# trackuino_micro_sensor_chip_mk2.net
KiCad netlist of a schematic drawn in EAGLE
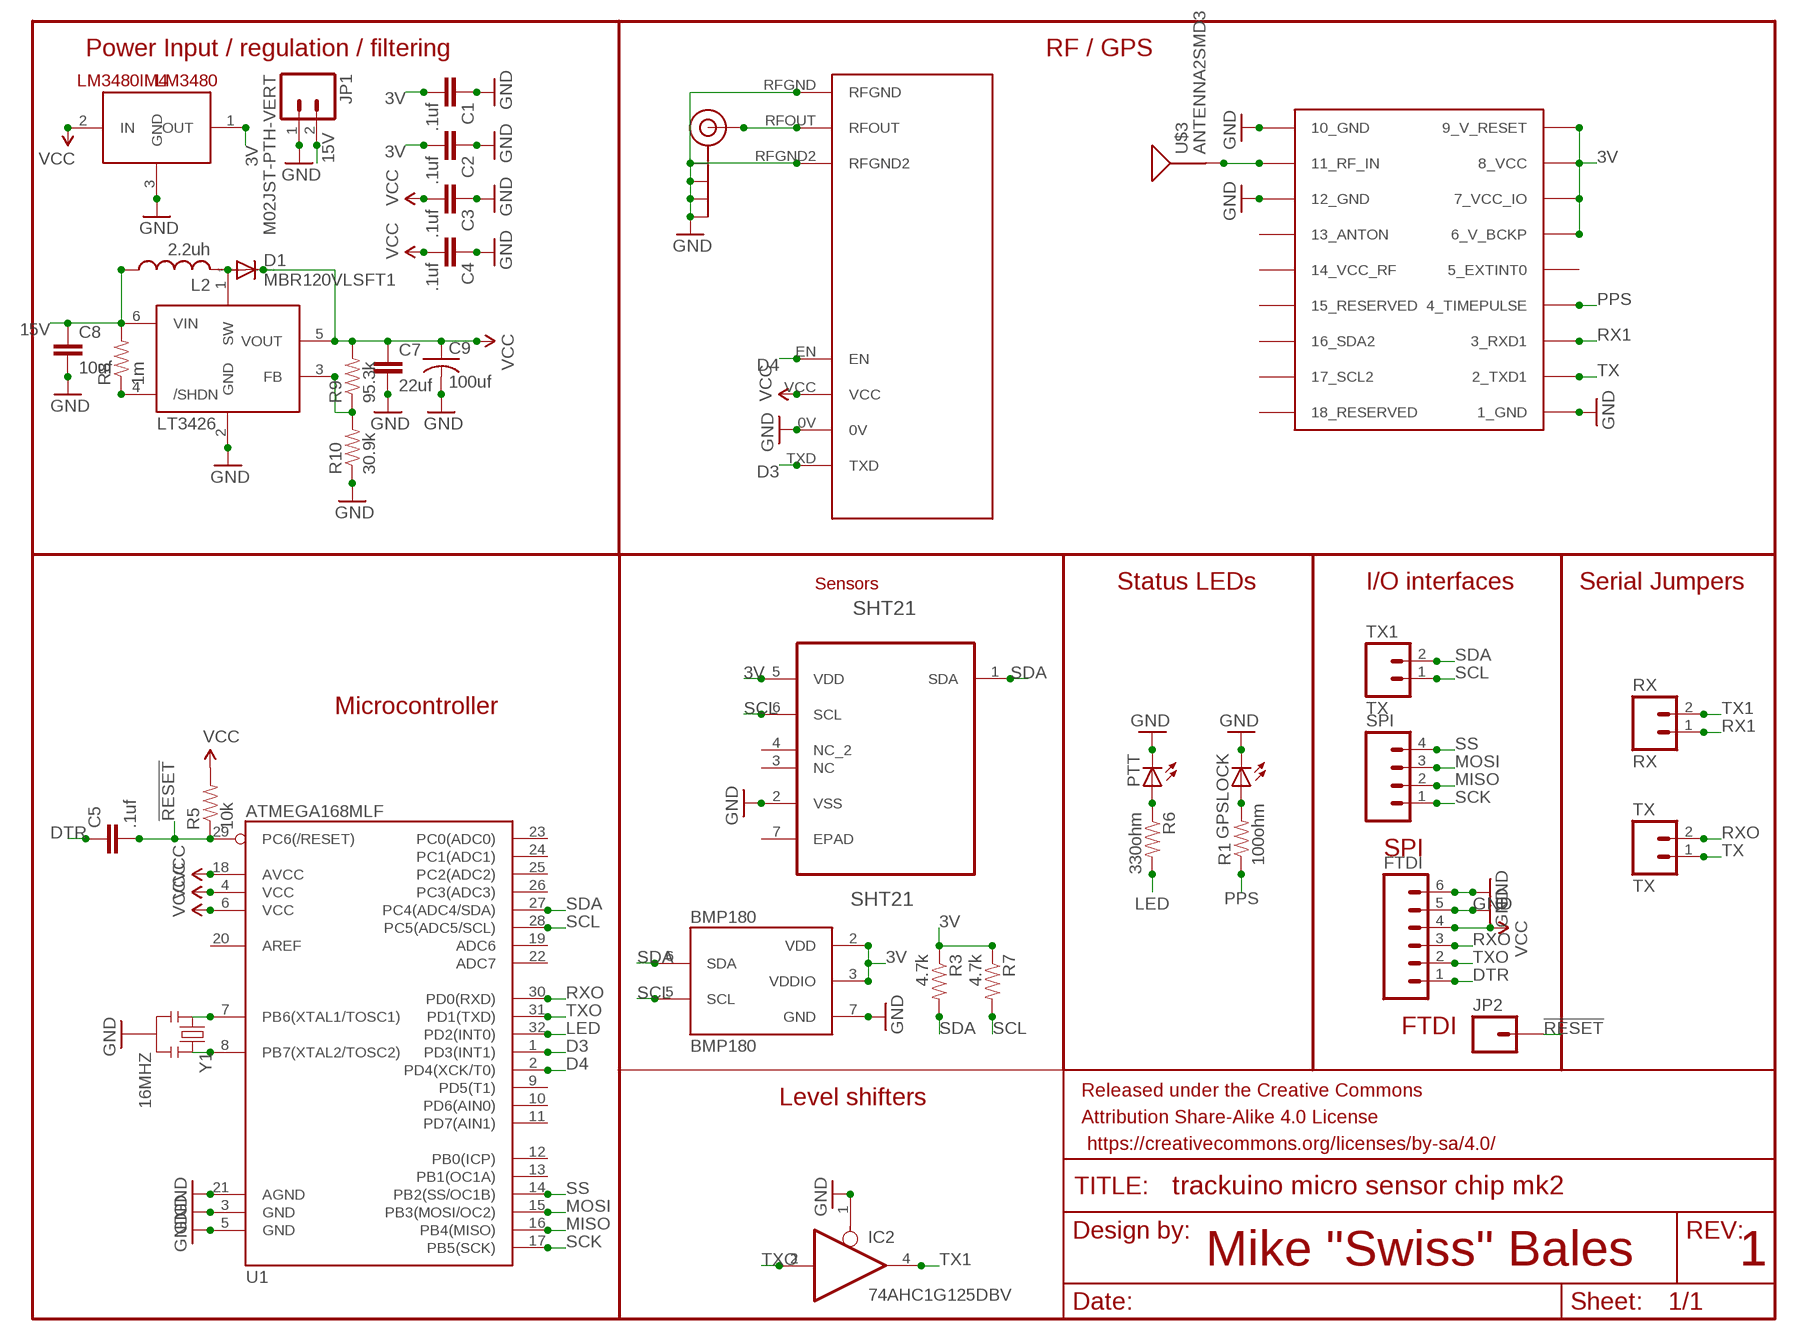
[diagram p0: schematic, sheet 1]

(export (version "E")
  (design (tool "Eeschema 10.0.6"))
  (components
    (comp (ref "BMP180")
      (value "BMP180")
      (footprint "eagle-import:BMP180")
      (libsource (lib "eagle-import") (part "BMP180"))
    )
    (comp (ref "C1")
      (value ".1uf")
      (footprint "eagle-import:0805")
      (libsource (lib "eagle-import") (part "CAP0805"))
    )
    (comp (ref "C2")
      (value ".1uf")
      (footprint "eagle-import:0805")
      (libsource (lib "eagle-import") (part "CAP0805"))
    )
    (comp (ref "C3")
      (value ".1uf")
      (footprint "eagle-import:0805")
      (libsource (lib "eagle-import") (part "CAP0805"))
    )
    (comp (ref "C4")
      (value ".1uf")
      (footprint "eagle-import:0805")
      (libsource (lib "eagle-import") (part "CAP0805"))
    )
    (comp (ref "C5")
      (value ".1uf")
      (footprint "eagle-import:0805")
      (libsource (lib "eagle-import") (part "CAP0805"))
    )
    (comp (ref "C7")
      (value "22uf")
      (footprint "eagle-import:0805")
      (libsource (lib "eagle-import") (part "CAP0805"))
    )
    (comp (ref "C8")
      (value "10uf")
      (footprint "eagle-import:0805")
      (libsource (lib "eagle-import") (part "CAP0805"))
    )
    (comp (ref "C9")
      (value "100uf")
      (footprint "eagle-import:C1206")
      (libsource (lib "eagle-import") (part "C-USC1206"))
    )
    (comp (ref "D1")
      (value "MBR120VLSFT1")
      (footprint "eagle-import:SOD123")
      (libsource (lib "eagle-import") (part "DIODE-SOD123"))
    )
    (comp (ref "FRAME1")
      (value "FRAME-LETTER")
      (footprint "eagle-import:CREATIVE_COMMONS")
      (libsource (lib "eagle-import") (part "FRAME-LETTER"))
    )
    (comp (ref "FTDI")
      (value "M06NO_SILK_FEMALE_PTH")
      (footprint "eagle-import:1X06_NO_SILK")
      (libsource (lib "eagle-import") (part "M06NO_SILK_FEMALE_PTH"))
    )
    (comp (ref "GPSLOCK")
      (value "LEDCHIP-LED0805")
      (footprint "eagle-import:CHIP-LED0805")
      (libsource (lib "eagle-import") (part "LEDCHIP-LED0805"))
    )
    (comp (ref "IC2")
      (value "74AHC1G125DBV")
      (footprint "eagle-import:SOT23-5")
      (libsource (lib "eagle-import") (part "741G125DBVAHC"))
    )
    (comp (ref "J$1")
      (value "SMA_EDGE")
      (footprint "eagle-import:SMA-EDGE")
      (libsource (lib "eagle-import") (part "SMA_EDGE"))
    )
    (comp (ref "JP1")
      (value "M02JST-PTH-VERT")
      (footprint "eagle-import:JST-2-PTH-VERT")
      (libsource (lib "eagle-import") (part "M02JST-PTH-VERT"))
    )
    (comp (ref "JP2")
      (value "M01PTH")
      (footprint "eagle-import:1X01")
      (libsource (lib "eagle-import") (part "M01PTH"))
    )
    (comp (ref "L2")
      (value "2.2uh")
      (footprint "eagle-import:L1812")
      (libsource (lib "eagle-import") (part "L-USL1812"))
    )
    (comp (ref "LM3480")
      (value "LM3480IM4")
      (footprint "eagle-import:SOT23-3")
      (libsource (lib "eagle-import") (part "LM3480IM4"))
    )
    (comp (ref "LT3426")
      (value "LT3426")
      (footprint "eagle-import:SOT23-6")
      (libsource (lib "eagle-import") (part "LT3426"))
    )
    (comp (ref "PTT")
      (value "LEDCHIP-LED0805")
      (footprint "eagle-import:CHIP-LED0805")
      (libsource (lib "eagle-import") (part "LEDCHIP-LED0805"))
    )
    (comp (ref "R1")
      (value "100ohm")
      (footprint "eagle-import:0805")
      (libsource (lib "eagle-import") (part "RESISTOR0805-RES"))
    )
    (comp (ref "R3")
      (value "4.7k")
      (footprint "eagle-import:0805")
      (libsource (lib "eagle-import") (part "RESISTOR0805-RES"))
    )
    (comp (ref "R5")
      (value "10k")
      (footprint "eagle-import:0805")
      (libsource (lib "eagle-import") (part "RESISTOR0805-RES"))
    )
    (comp (ref "R6")
      (value "330ohm")
      (footprint "eagle-import:0805")
      (libsource (lib "eagle-import") (part "RESISTOR0805-RES"))
    )
    (comp (ref "R7")
      (value "4.7k")
      (footprint "eagle-import:0805")
      (libsource (lib "eagle-import") (part "RESISTOR0805-RES"))
    )
    (comp (ref "R8")
      (value "1m")
      (footprint "eagle-import:0805")
      (libsource (lib "eagle-import") (part "RESISTOR0805-RES"))
    )
    (comp (ref "R9")
      (value "95.3k")
      (footprint "eagle-import:0805")
      (libsource (lib "eagle-import") (part "RESISTOR0805-RES"))
    )
    (comp (ref "R10")
      (value "30.9k")
      (footprint "eagle-import:0805")
      (libsource (lib "eagle-import") (part "RESISTOR0805-RES"))
    )
    (comp (ref "RX")
      (value "RX")
      (footprint "eagle-import:JST-2-PTH-VERT")
      (libsource (lib "eagle-import") (part "M02JST-PTH-VERT"))
    )
    (comp (ref "SHT21")
      (value "SHT21")
      (footprint "eagle-import:DFN300X300X110-7N")
      (libsource (lib "eagle-import") (part "SHT21"))
    )
    (comp (ref "SPI")
      (value "M04JST-PTH-VERT")
      (footprint "eagle-import:JST-4-PTH-VERT")
      (libsource (lib "eagle-import") (part "M04JST-PTH-VERT"))
    )
    (comp (ref "TX")
      (value "TX")
      (footprint "eagle-import:JST-2-PTH-VERT")
      (libsource (lib "eagle-import") (part "M02JST-PTH-VERT"))
    )
    (comp (ref "TX1")
      (value "TX")
      (footprint "eagle-import:JST-2-PTH-VERT")
      (libsource (lib "eagle-import") (part "M02JST-PTH-VERT"))
    )
    (comp (ref "U$1")
      (value "UBLOX_MAX")
      (footprint "eagle-import:UBLOX_MAX")
      (libsource (lib "eagle-import") (part "UBLOX_MAX"))
    )
    (comp (ref "U$2")
      (value "RADIOMETRIX-HX1")
      (footprint "eagle-import:RADIOMETRIX-HX1")
      (libsource (lib "eagle-import") (part "RADIOMETRIX-HX1"))
    )
    (comp (ref "U$3")
      (value "ANTENNA2SMD3")
      (footprint "eagle-import:ANTENNA-CHIP4")
      (libsource (lib "eagle-import") (part "ANTENNA2SMD3"))
    )
    (comp (ref "U1")
      (value "ATMEGA168MLF")
      (footprint "eagle-import:MLF32")
      (libsource (lib "eagle-import") (part "ATMEGA168MLF"))
    )
    (comp (ref "Y1")
      (value "16MHZ")
      (footprint "eagle-import:RESONATOR-SMD")
      (libsource (lib "eagle-import") (part "RESONATOR16MHZ"))
    )
  )
  (nets
    (net (code "1") (name "/3V") (class "Default")
      (node (ref "BMP180") (pin "2") (pinfunction "VDD_2") (pintype "power_in"))
      (node (ref "BMP180") (pin "3") (pinfunction "VDDIO_3") (pintype "power_in"))
      (node (ref "C1") (pin "2") (pinfunction "2_2") (pintype "passive"))
      (node (ref "C2") (pin "2") (pinfunction "2_2") (pintype "passive"))
      (node (ref "LM3480") (pin "1") (pinfunction "OUT_1") (pintype "bidirectional"))
      (node (ref "R3") (pin "1") (pinfunction "1_1") (pintype "passive"))
      (node (ref "R7") (pin "1") (pinfunction "1_1") (pintype "passive"))
      (node (ref "SHT21") (pin "5") (pinfunction "VDD_5") (pintype "power_in"))
      (node (ref "U$1") (pin "6_V_BCKP") (pinfunction "6_V_BCKP_6_V_BCKP") (pintype "bidirectional"))
      (node (ref "U$1") (pin "7_VCC_IO") (pinfunction "7_VCC_IO_7_VCC_IO") (pintype "power_in"))
      (node (ref "U$1") (pin "8_VCC") (pinfunction "8_VCC_8_VCC") (pintype "power_in"))
      (node (ref "U$1") (pin "9_V_RESET") (pinfunction "9_V_RESET_9_V_RESET") (pintype "power_in"))
    )
    (net (code "2") (name "/15V") (class "Default")
      (node (ref "C8") (pin "1") (pinfunction "1_1") (pintype "passive"))
      (node (ref "JP1") (pin "2") (pinfunction "2_2") (pintype "passive"))
      (node (ref "L2") (pin "1") (pinfunction "1_1") (pintype "passive"))
      (node (ref "LT3426") (pin "6") (pinfunction "VIN_6") (pintype "input"))
      (node (ref "R8") (pin "2") (pinfunction "2_2") (pintype "passive"))
    )
    (net (code "3") (name "/D3") (class "Default")
      (node (ref "U$2") (pin "TXD") (pinfunction "TXD_TXD") (pintype "bidirectional"))
      (node (ref "U1") (pin "1") (pinfunction "PD3(INT1)_1") (pintype "bidirectional"))
    )
    (net (code "4") (name "/D4") (class "Default")
      (node (ref "U$2") (pin "EN") (pinfunction "EN_EN") (pintype "bidirectional"))
      (node (ref "U1") (pin "2") (pinfunction "PD4(XCK/T0)_2") (pintype "bidirectional"))
    )
    (net (code "5") (name "/DTR") (class "Default")
      (node (ref "C5") (pin "1") (pinfunction "1_1") (pintype "passive"))
      (node (ref "FTDI") (pin "1") (pinfunction "1_1") (pintype "passive"))
    )
    (net (code "6") (name "/LED") (class "Default")
      (node (ref "R6") (pin "2") (pinfunction "2_2") (pintype "passive"))
      (node (ref "U1") (pin "32") (pinfunction "PD2(INT0)_32") (pintype "bidirectional"))
    )
    (net (code "7") (name "/MISO") (class "Default")
      (node (ref "SPI") (pin "2") (pinfunction "2_2") (pintype "passive"))
      (node (ref "U1") (pin "16") (pinfunction "PB4(MISO)_16") (pintype "bidirectional"))
    )
    (net (code "8") (name "/MOSI") (class "Default")
      (node (ref "SPI") (pin "3") (pinfunction "3_3") (pintype "passive"))
      (node (ref "U1") (pin "15") (pinfunction "PB3(MOSI/OC2)_15") (pintype "bidirectional"))
    )
    (net (code "9") (name "/PPS") (class "Default")
      (node (ref "R1") (pin "1") (pinfunction "1_1") (pintype "passive"))
      (node (ref "U$1") (pin "4_TIMEPULSE") (pinfunction "4_TIMEPULSE_4_TIMEPULSE") (pintype "bidirectional"))
    )
    (net (code "10") (name "/RX1") (class "Default")
      (node (ref "RX") (pin "1") (pinfunction "1_1") (pintype "passive"))
      (node (ref "U$1") (pin "3_RXD1") (pinfunction "3_RXD1_3_RXD1") (pintype "bidirectional"))
    )
    (net (code "11") (name "/RXO") (class "Default")
      (node (ref "FTDI") (pin "3") (pinfunction "3_3") (pintype "passive"))
      (node (ref "TX") (pin "2") (pinfunction "2_2") (pintype "passive"))
      (node (ref "U1") (pin "30") (pinfunction "PD0(RXD)_30") (pintype "bidirectional"))
    )
    (net (code "12") (name "/SCK") (class "Default")
      (node (ref "SPI") (pin "1") (pinfunction "1_1") (pintype "passive"))
      (node (ref "U1") (pin "17") (pinfunction "PB5(SCK)_17") (pintype "bidirectional"))
    )
    (net (code "13") (name "/SCL") (class "Default")
      (node (ref "BMP180") (pin "5") (pinfunction "SCL_5") (pintype "input"))
      (node (ref "R7") (pin "2") (pinfunction "2_2") (pintype "passive"))
      (node (ref "SHT21") (pin "6") (pinfunction "SCL_6") (pintype "input"))
      (node (ref "TX1") (pin "1") (pinfunction "1_1") (pintype "passive"))
      (node (ref "U1") (pin "28") (pinfunction "PC5(ADC5/SCL)_28") (pintype "bidirectional"))
    )
    (net (code "14") (name "/SDA") (class "Default")
      (node (ref "BMP180") (pin "6") (pinfunction "SDA_6") (pintype "bidirectional"))
      (node (ref "R3") (pin "2") (pinfunction "2_2") (pintype "passive"))
      (node (ref "SHT21") (pin "1") (pinfunction "SDA_1") (pintype "bidirectional"))
      (node (ref "TX1") (pin "2") (pinfunction "2_2") (pintype "passive"))
      (node (ref "U1") (pin "27") (pinfunction "PC4(ADC4/SDA)_27") (pintype "bidirectional"))
    )
    (net (code "15") (name "/SS") (class "Default")
      (node (ref "SPI") (pin "4") (pinfunction "4_4") (pintype "passive"))
      (node (ref "U1") (pin "14") (pinfunction "PB2(SS/OC1B)_14") (pintype "bidirectional"))
    )
    (net (code "16") (name "/TX") (class "Default")
      (node (ref "TX") (pin "1") (pinfunction "1_1") (pintype "passive"))
      (node (ref "U$1") (pin "2_TXD1") (pinfunction "2_TXD1_2_TXD1") (pintype "bidirectional"))
    )
    (net (code "17") (name "/TX1") (class "Default")
      (node (ref "IC2") (pin "4") (pinfunction "O_4") (pintype "tri_state"))
      (node (ref "RX") (pin "2") (pinfunction "2_2") (pintype "passive"))
    )
    (net (code "18") (name "/TXO") (class "Default")
      (node (ref "FTDI") (pin "2") (pinfunction "2_2") (pintype "passive"))
      (node (ref "IC2") (pin "2") (pinfunction "I_2") (pintype "input"))
      (node (ref "U1") (pin "31") (pinfunction "PD1(TXD)_31") (pintype "bidirectional"))
    )
    (net (code "19") (name "/~{RESET}") (class "Default")
      (node (ref "C5") (pin "2") (pinfunction "2_2") (pintype "passive"))
      (node (ref "JP2") (pin "1") (pinfunction "1_1") (pintype "passive"))
      (node (ref "R5") (pin "1") (pinfunction "1_1") (pintype "passive"))
      (node (ref "U1") (pin "29") (pinfunction "PC6(/RESET)_29") (pintype "bidirectional"))
    )
    (net (code "20") (name "GND") (class "Default")
      (node (ref "BMP180") (pin "7") (pinfunction "GND_7") (pintype "power_in"))
      (node (ref "C1") (pin "1") (pinfunction "1_1") (pintype "passive"))
      (node (ref "C2") (pin "1") (pinfunction "1_1") (pintype "passive"))
      (node (ref "C3") (pin "1") (pinfunction "1_1") (pintype "passive"))
      (node (ref "C4") (pin "1") (pinfunction "1_1") (pintype "passive"))
      (node (ref "C7") (pin "2") (pinfunction "2_2") (pintype "passive"))
      (node (ref "C8") (pin "2") (pinfunction "2_2") (pintype "passive"))
      (node (ref "C9") (pin "2") (pinfunction "2_2") (pintype "passive"))
      (node (ref "FTDI") (pin "5") (pinfunction "5_5") (pintype "passive"))
      (node (ref "FTDI") (pin "6") (pinfunction "6_6") (pintype "passive"))
      (node (ref "GPSLOCK") (pin "C") (pinfunction "C_C") (pintype "passive"))
      (node (ref "IC2") (pin "1") (pinfunction "OE_1") (pintype "input"))
      (node (ref "J$1") (pin "GND@0") (pinfunction "GND_GND@0") (pintype "bidirectional"))
      (node (ref "J$1") (pin "GND@1") (pinfunction "GND_GND@1") (pintype "bidirectional"))
      (node (ref "J$1") (pin "GND@2") (pinfunction "GND_GND@2") (pintype "bidirectional"))
      (node (ref "J$1") (pin "GND@3") (pinfunction "GND_GND@3") (pintype "bidirectional"))
      (node (ref "JP1") (pin "1") (pinfunction "1_1") (pintype "passive"))
      (node (ref "LM3480") (pin "3") (pinfunction "GND_3") (pintype "bidirectional"))
      (node (ref "LT3426") (pin "2") (pinfunction "GND_2") (pintype "power_in"))
      (node (ref "PTT") (pin "C") (pinfunction "C_C") (pintype "passive"))
      (node (ref "R10") (pin "1") (pinfunction "1_1") (pintype "passive"))
      (node (ref "SHT21") (pin "2") (pinfunction "VSS_2") (pintype "power_in"))
      (node (ref "U$1") (pin "10_GND") (pinfunction "10_GND_10_GND") (pintype "power_in"))
      (node (ref "U$1") (pin "12_GND") (pinfunction "12_GND_12_GND") (pintype "power_in"))
      (node (ref "U$1") (pin "1_GND") (pinfunction "1_GND_1_GND") (pintype "power_in"))
      (node (ref "U$2") (pin "0V") (pinfunction "0V_0V") (pintype "bidirectional"))
      (node (ref "U$2") (pin "RFGND") (pinfunction "RFGND_RFGND") (pintype "bidirectional"))
      (node (ref "U$2") (pin "RFGND2") (pinfunction "RFGND2_RFGND2") (pintype "bidirectional"))
      (node (ref "U1") (pin "21") (pinfunction "AGND_21") (pintype "bidirectional"))
      (node (ref "U1") (pin "3") (pinfunction "GND_3") (pintype "bidirectional"))
      (node (ref "U1") (pin "5") (pinfunction "GND_5") (pintype "bidirectional"))
      (node (ref "Y1") (pin "2") (pinfunction "2_2") (pintype "passive"))
    )
    (net (code "21") (name "Net-(GPSLOCK-PadA)") (class "Default")
      (node (ref "GPSLOCK") (pin "A") (pinfunction "A_A") (pintype "passive"))
      (node (ref "R1") (pin "2") (pinfunction "2_2") (pintype "passive"))
    )
    (net (code "22") (name "Net-(J$1-SIGNAL)") (class "Default")
      (node (ref "J$1") (pin "SIG") (pinfunction "SIGNAL_SIG") (pintype "bidirectional"))
      (node (ref "U$2") (pin "RFOUT") (pinfunction "RFOUT_RFOUT") (pintype "bidirectional"))
    )
    (net (code "23") (name "Net-(LT3426-FB)") (class "Default")
      (node (ref "LT3426") (pin "3") (pinfunction "FB_3") (pintype "input"))
      (node (ref "R10") (pin "2") (pinfunction "2_2") (pintype "passive"))
      (node (ref "R9") (pin "1") (pinfunction "1_1") (pintype "passive"))
    )
    (net (code "24") (name "Net-(LT3426-SW)") (class "Default")
      (node (ref "D1") (pin "A") (pinfunction "A_A") (pintype "passive"))
      (node (ref "L2") (pin "2") (pinfunction "2_2") (pintype "passive"))
      (node (ref "LT3426") (pin "1") (pinfunction "SW_1") (pintype "output"))
    )
    (net (code "25") (name "Net-(LT3426-{slash}SHDN)") (class "Default")
      (node (ref "LT3426") (pin "4") (pinfunction "/SHDN_4") (pintype "input"))
      (node (ref "R8") (pin "1") (pinfunction "1_1") (pintype "passive"))
    )
    (net (code "26") (name "Net-(PTT-PadA)") (class "Default")
      (node (ref "PTT") (pin "A") (pinfunction "A_A") (pintype "passive"))
      (node (ref "R6") (pin "1") (pinfunction "1_1") (pintype "passive"))
    )
    (net (code "27") (name "Net-(U$3-SIGNAL)") (class "Default")
      (node (ref "U$1") (pin "11_RF_IN") (pinfunction "11_RF_IN_11_RF_IN") (pintype "bidirectional"))
      (node (ref "U$3") (pin "SIG") (pinfunction "SIGNAL_SIG") (pintype "bidirectional"))
    )
    (net (code "28") (name "Net-(U1-PB6(XTAL1{slash}TOSC1))") (class "Default")
      (node (ref "U1") (pin "7") (pinfunction "PB6(XTAL1/TOSC1)_7") (pintype "bidirectional"))
      (node (ref "Y1") (pin "1") (pinfunction "1_1") (pintype "passive"))
    )
    (net (code "29") (name "Net-(U1-PB7(XTAL2{slash}TOSC2))") (class "Default")
      (node (ref "U1") (pin "8") (pinfunction "PB7(XTAL2/TOSC2)_8") (pintype "bidirectional"))
      (node (ref "Y1") (pin "3") (pinfunction "3_3") (pintype "passive"))
    )
    (net (code "30") (name "VCC") (class "Default")
      (node (ref "C3") (pin "2") (pinfunction "2_2") (pintype "passive"))
      (node (ref "C4") (pin "2") (pinfunction "2_2") (pintype "passive"))
      (node (ref "C7") (pin "1") (pinfunction "1_1") (pintype "passive"))
      (node (ref "C9") (pin "1") (pinfunction "1_1") (pintype "passive"))
      (node (ref "D1") (pin "C") (pinfunction "C_C") (pintype "passive"))
      (node (ref "FTDI") (pin "4") (pinfunction "4_4") (pintype "passive"))
      (node (ref "LM3480") (pin "2") (pinfunction "IN_2") (pintype "bidirectional"))
      (node (ref "LT3426") (pin "5") (pinfunction "VOUT_5") (pintype "output"))
      (node (ref "R5") (pin "2") (pinfunction "2_2") (pintype "passive"))
      (node (ref "R9") (pin "2") (pinfunction "2_2") (pintype "passive"))
      (node (ref "U$2") (pin "VCC") (pinfunction "VCC_VCC") (pintype "bidirectional"))
      (node (ref "U1") (pin "18") (pinfunction "AVCC_18") (pintype "bidirectional"))
      (node (ref "U1") (pin "4") (pinfunction "VCC_4") (pintype "bidirectional"))
      (node (ref "U1") (pin "6") (pinfunction "VCC_6") (pintype "bidirectional"))
    )
    (net (code "31") (name "unconnected-(SHT21-EPAD-Pad7)") (class "Default")
      (node (ref "SHT21") (pin "7") (pinfunction "EPAD_7") (pintype "passive"))
    )
    (net (code "32") (name "unconnected-(SHT21-NC-Pad3)") (class "Default")
      (node (ref "SHT21") (pin "3") (pinfunction "NC_3") (pintype "no_connect"))
    )
    (net (code "33") (name "unconnected-(SHT21-NC_2-Pad4)") (class "Default")
      (node (ref "SHT21") (pin "4") (pinfunction "NC_2_4") (pintype "no_connect"))
    )
    (net (code "34") (name "unconnected-(U$1-Pad5_EXTINT0)") (class "Default")
      (node (ref "U$1") (pin "5_EXTINT0") (pinfunction "5_EXTINT0_5_EXTINT0") (pintype "bidirectional"))
    )
    (net (code "35") (name "unconnected-(U$1-Pad13_ANTON)") (class "Default")
      (node (ref "U$1") (pin "13_ANTON") (pinfunction "13_ANTON_13_ANTON") (pintype "bidirectional"))
    )
    (net (code "36") (name "unconnected-(U$1-Pad14_VCC_RF)") (class "Default")
      (node (ref "U$1") (pin "14_VCC_RF") (pinfunction "14_VCC_RF_14_VCC_RF") (pintype "bidirectional"))
    )
    (net (code "37") (name "unconnected-(U$1-Pad15_RESERVED)") (class "Default")
      (node (ref "U$1") (pin "15_RESERVED") (pinfunction "15_RESERVED_15_RESERVED") (pintype "bidirectional"))
    )
    (net (code "38") (name "unconnected-(U$1-Pad16_SDA2)") (class "Default")
      (node (ref "U$1") (pin "16_SDA2") (pinfunction "16_SDA2_16_SDA2") (pintype "bidirectional"))
    )
    (net (code "39") (name "unconnected-(U$1-Pad17_SCL2)") (class "Default")
      (node (ref "U$1") (pin "17_SCL2") (pinfunction "17_SCL2_17_SCL2") (pintype "bidirectional"))
    )
    (net (code "40") (name "unconnected-(U$1-Pad18_RESERVED)") (class "Default")
      (node (ref "U$1") (pin "18_RESERVED") (pinfunction "18_RESERVED_18_RESERVED") (pintype "bidirectional"))
    )
    (net (code "41") (name "unconnected-(U1-ADC6-Pad19)") (class "Default")
      (node (ref "U1") (pin "19") (pinfunction "ADC6_19") (pintype "bidirectional"))
    )
    (net (code "42") (name "unconnected-(U1-ADC7-Pad22)") (class "Default")
      (node (ref "U1") (pin "22") (pinfunction "ADC7_22") (pintype "bidirectional"))
    )
    (net (code "43") (name "unconnected-(U1-AREF-Pad20)") (class "Default")
      (node (ref "U1") (pin "20") (pinfunction "AREF_20") (pintype "bidirectional"))
    )
    (net (code "44") (name "unconnected-(U1-PB0(ICP)-Pad12)") (class "Default")
      (node (ref "U1") (pin "12") (pinfunction "PB0(ICP)_12") (pintype "bidirectional"))
    )
    (net (code "45") (name "unconnected-(U1-PB1(OC1A)-Pad13)") (class "Default")
      (node (ref "U1") (pin "13") (pinfunction "PB1(OC1A)_13") (pintype "bidirectional"))
    )
    (net (code "46") (name "unconnected-(U1-PC0(ADC0)-Pad23)") (class "Default")
      (node (ref "U1") (pin "23") (pinfunction "PC0(ADC0)_23") (pintype "bidirectional"))
    )
    (net (code "47") (name "unconnected-(U1-PC1(ADC1)-Pad24)") (class "Default")
      (node (ref "U1") (pin "24") (pinfunction "PC1(ADC1)_24") (pintype "bidirectional"))
    )
    (net (code "48") (name "unconnected-(U1-PC2(ADC2)-Pad25)") (class "Default")
      (node (ref "U1") (pin "25") (pinfunction "PC2(ADC2)_25") (pintype "bidirectional"))
    )
    (net (code "49") (name "unconnected-(U1-PC3(ADC3)-Pad26)") (class "Default")
      (node (ref "U1") (pin "26") (pinfunction "PC3(ADC3)_26") (pintype "bidirectional"))
    )
    (net (code "50") (name "unconnected-(U1-PD5(T1)-Pad9)") (class "Default")
      (node (ref "U1") (pin "9") (pinfunction "PD5(T1)_9") (pintype "bidirectional"))
    )
    (net (code "51") (name "unconnected-(U1-PD6(AIN0)-Pad10)") (class "Default")
      (node (ref "U1") (pin "10") (pinfunction "PD6(AIN0)_10") (pintype "bidirectional"))
    )
    (net (code "52") (name "unconnected-(U1-PD7(AIN1)-Pad11)") (class "Default")
      (node (ref "U1") (pin "11") (pinfunction "PD7(AIN1)_11") (pintype "bidirectional"))
    )
  )
)
